# Nucleo_DCO_EX1.net
KiCad netlist of a schematic drawn in EAGLE
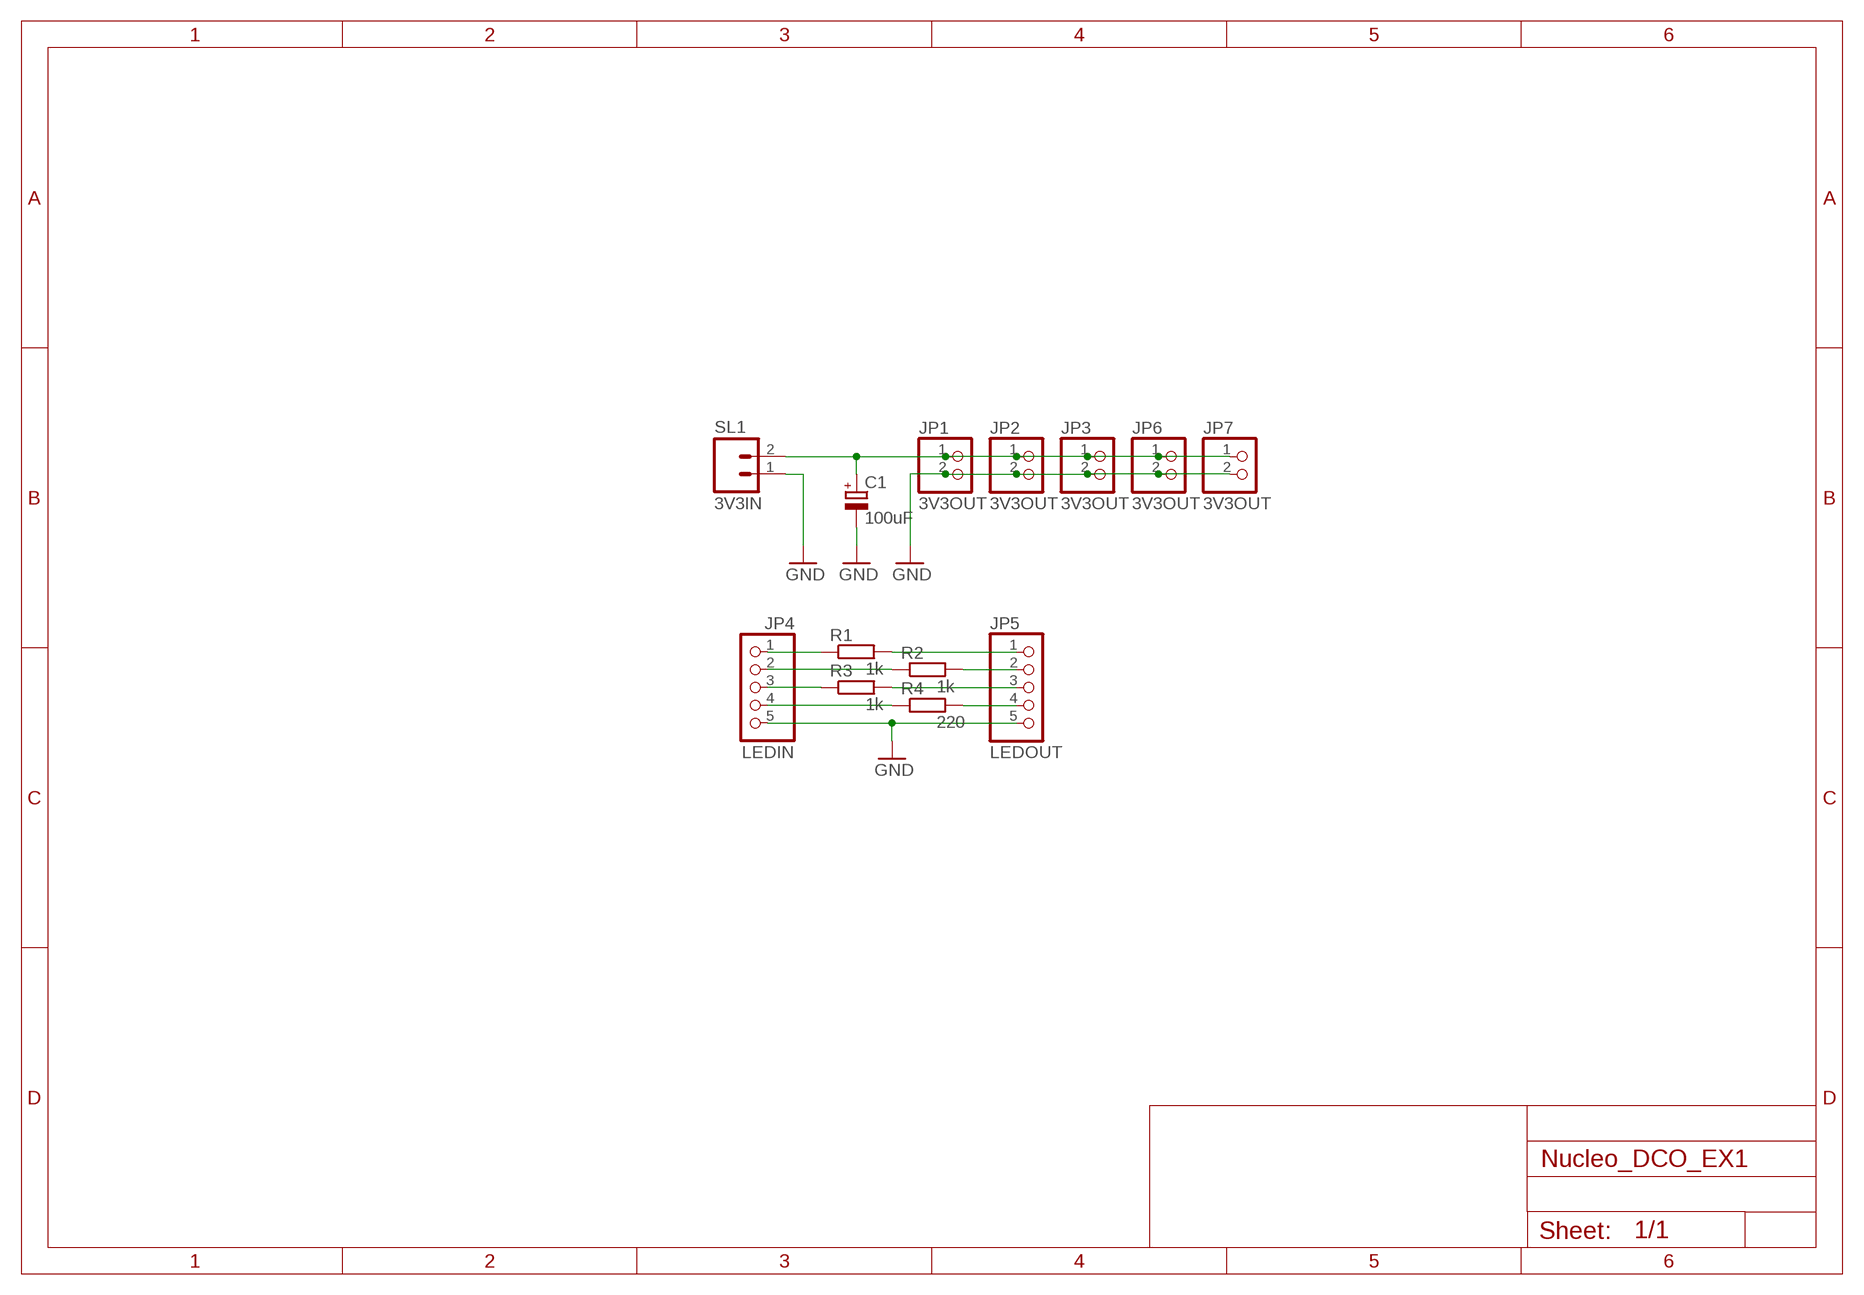
[diagram p0: schematic, sheet 1]

(export (version "E")
  (design (tool "Eeschema 10.0.6"))
  (components
    (comp (ref "C1")
      (value "100uF")
      (footprint "eagle-import:SANYO-OSCON_C6")
      (libsource (lib "eagle-import") (part "CPOL-EUSANYO_C6"))
    )
    (comp (ref "JP1")
      (value "3V3OUT")
      (footprint "eagle-import:1X02")
      (libsource (lib "eagle-import") (part "PINHD-1X2"))
    )
    (comp (ref "JP2")
      (value "3V3OUT")
      (footprint "eagle-import:1X02")
      (libsource (lib "eagle-import") (part "PINHD-1X2"))
    )
    (comp (ref "JP3")
      (value "3V3OUT")
      (footprint "eagle-import:1X02")
      (libsource (lib "eagle-import") (part "PINHD-1X2"))
    )
    (comp (ref "JP4")
      (value "LEDIN")
      (footprint "eagle-import:1X05")
      (libsource (lib "eagle-import") (part "PINHD-1X5"))
    )
    (comp (ref "JP5")
      (value "LEDOUT")
      (footprint "eagle-import:1X05")
      (libsource (lib "eagle-import") (part "PINHD-1X5"))
    )
    (comp (ref "JP6")
      (value "3V3OUT")
      (footprint "eagle-import:1X02")
      (libsource (lib "eagle-import") (part "PINHD-1X2"))
    )
    (comp (ref "JP7")
      (value "3V3OUT")
      (footprint "eagle-import:1X02")
      (libsource (lib "eagle-import") (part "PINHD-1X2"))
    )
    (comp (ref "R1")
      (value "1k")
      (footprint "eagle-import:0207_7")
      (libsource (lib "eagle-import") (part "R-EU_0207/7"))
    )
    (comp (ref "R2")
      (value "1k")
      (footprint "eagle-import:0207_7")
      (libsource (lib "eagle-import") (part "R-EU_0207/7"))
    )
    (comp (ref "R3")
      (value "1k")
      (footprint "eagle-import:0207_7")
      (libsource (lib "eagle-import") (part "R-EU_0207/7"))
    )
    (comp (ref "R4")
      (value "220")
      (footprint "eagle-import:0207_7")
      (libsource (lib "eagle-import") (part "R-EU_0207/7"))
    )
    (comp (ref "SL1")
      (value "3V3IN")
      (footprint "eagle-import:02P")
      (libsource (lib "eagle-import") (part "M02"))
    )
  )
  (nets
    (net (code "1") (name "GND") (class "Default")
      (node (ref "C1") (pin "-") (pinfunction "-_-") (pintype "passive"))
      (node (ref "JP1") (pin "2") (pinfunction "2_2") (pintype "passive"))
      (node (ref "JP2") (pin "2") (pinfunction "2_2") (pintype "passive"))
      (node (ref "JP3") (pin "2") (pinfunction "2_2") (pintype "passive"))
      (node (ref "JP4") (pin "5") (pinfunction "5_5") (pintype "passive"))
      (node (ref "JP5") (pin "5") (pinfunction "5_5") (pintype "passive"))
      (node (ref "JP6") (pin "2") (pinfunction "2_2") (pintype "passive"))
      (node (ref "JP7") (pin "2") (pinfunction "2_2") (pintype "passive"))
      (node (ref "SL1") (pin "1") (pinfunction "1_1") (pintype "passive"))
    )
    (net (code "2") (name "Net-(C1-Pad+)") (class "Default")
      (node (ref "C1") (pin "+") (pinfunction "+_+") (pintype "passive"))
      (node (ref "JP1") (pin "1") (pinfunction "1_1") (pintype "passive"))
      (node (ref "JP2") (pin "1") (pinfunction "1_1") (pintype "passive"))
      (node (ref "JP3") (pin "1") (pinfunction "1_1") (pintype "passive"))
      (node (ref "JP6") (pin "1") (pinfunction "1_1") (pintype "passive"))
      (node (ref "JP7") (pin "1") (pinfunction "1_1") (pintype "passive"))
      (node (ref "SL1") (pin "2") (pinfunction "2_2") (pintype "passive"))
    )
    (net (code "3") (name "Net-(JP4-Pad1)") (class "Default")
      (node (ref "JP4") (pin "1") (pinfunction "1_1") (pintype "passive"))
      (node (ref "R1") (pin "1") (pinfunction "1_1") (pintype "passive"))
    )
    (net (code "4") (name "Net-(JP4-Pad2)") (class "Default")
      (node (ref "JP4") (pin "2") (pinfunction "2_2") (pintype "passive"))
      (node (ref "R2") (pin "1") (pinfunction "1_1") (pintype "passive"))
    )
    (net (code "5") (name "Net-(JP4-Pad3)") (class "Default")
      (node (ref "JP4") (pin "3") (pinfunction "3_3") (pintype "passive"))
      (node (ref "R3") (pin "1") (pinfunction "1_1") (pintype "passive"))
    )
    (net (code "6") (name "Net-(JP4-Pad4)") (class "Default")
      (node (ref "JP4") (pin "4") (pinfunction "4_4") (pintype "passive"))
      (node (ref "R4") (pin "1") (pinfunction "1_1") (pintype "passive"))
    )
    (net (code "7") (name "Net-(JP5-Pad1)") (class "Default")
      (node (ref "JP5") (pin "1") (pinfunction "1_1") (pintype "passive"))
      (node (ref "R1") (pin "2") (pinfunction "2_2") (pintype "passive"))
    )
    (net (code "8") (name "Net-(JP5-Pad2)") (class "Default")
      (node (ref "JP5") (pin "2") (pinfunction "2_2") (pintype "passive"))
      (node (ref "R2") (pin "2") (pinfunction "2_2") (pintype "passive"))
    )
    (net (code "9") (name "Net-(JP5-Pad3)") (class "Default")
      (node (ref "JP5") (pin "3") (pinfunction "3_3") (pintype "passive"))
      (node (ref "R3") (pin "2") (pinfunction "2_2") (pintype "passive"))
    )
    (net (code "10") (name "Net-(JP5-Pad4)") (class "Default")
      (node (ref "JP5") (pin "4") (pinfunction "4_4") (pintype "passive"))
      (node (ref "R4") (pin "2") (pinfunction "2_2") (pintype "passive"))
    )
  )
)
